# Zero_Crossing.net
KiCad netlist of a schematic drawn in Altium Designer
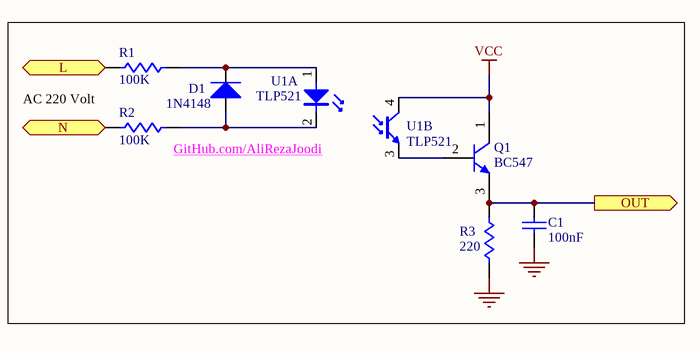
[diagram p0: Zero Crossing.SchDoc]

(export (version "E")
  (design (tool "Eeschema 10.0.6"))
  (components
    (comp (ref "C1")
      (value "100nF")
      (footprint "CAPNTO5.08-7.37x3.94")
      (description "Capacitor")
      (fields (field (name "MANUFACTURER") "Generic Components") (field (name "PUBLISHER") "Altium Limited"))
      (libsource (lib "Miscellaneous Devices") (part "Cap"))
    )
    (comp (ref "D1")
      (value "1N4148")
      (footprint "DIODE0.2_")
      (description "Default Diode")
      (fields (field (name "MANUFACTURER") "Generic Components") (field (name "PUBLISHER") "Altium Limited"))
      (libsource (lib "Miscellaneous Devices") (part "Diode"))
    )
    (comp (ref "Q1")
      (value "BC547")
      (footprint "TO92C")
      (description "Silicon Bipolar Transistor")
      (libsource (lib "my Libraries") (part "NPN"))
    )
    (comp (ref "R1")
      (value "100K")
      (footprint "AXIAL-0.4")
      (description "Resistor")
      (fields (field (name "MANUFACTURER") "Generic Components") (field (name "PUBLISHER") "Altium Limited"))
      (libsource (lib "Miscellaneous Devices") (part "Res1"))
    )
    (comp (ref "R2")
      (value "100K")
      (footprint "AXIAL-0.4")
      (description "Resistor")
      (fields (field (name "MANUFACTURER") "Generic Components") (field (name "PUBLISHER") "Altium Limited"))
      (libsource (lib "Miscellaneous Devices") (part "Res1"))
    )
    (comp (ref "R3")
      (value "220")
      (footprint "AXIAL-0.4")
      (description "Resistor")
      (fields (field (name "MANUFACTURER") "Generic Components") (field (name "PUBLISHER") "Altium Limited"))
      (libsource (lib "Miscellaneous Devices") (part "Res1"))
    )
    (comp (ref "U1")
      (value "TLP521")
      (footprint "DIP-4")
      (fields (field (name "PUBLISHER") "Altium Limited"))
      (libsource (lib "my Libraries") (part "Optoisolator"))
    )
  )
  (nets
    (net (code "1") (name "/L") (class "Default")
      (node (ref "R1") (pin "1") (pinfunction "1_1") (pintype "passive"))
    )
    (net (code "2") (name "/N") (class "Default")
      (node (ref "R2") (pin "1") (pinfunction "1_1") (pintype "passive"))
    )
    (net (code "3") (name "/OUT") (class "Default")
      (node (ref "C1") (pin "2") (pinfunction "2_2") (pintype "passive"))
      (node (ref "Q1") (pin "3") (pinfunction "E_3") (pintype "passive"))
      (node (ref "R3") (pin "1") (pinfunction "1_1") (pintype "passive"))
    )
    (net (code "4") (name "GND") (class "Default")
      (node (ref "C1") (pin "1") (pinfunction "1_1") (pintype "passive"))
      (node (ref "R3") (pin "2") (pinfunction "2_2") (pintype "passive"))
    )
    (net (code "5") (name "Net-(D1-A)") (class "Default")
      (node (ref "D1") (pin "1") (pinfunction "A_1") (pintype "passive"))
      (node (ref "R2") (pin "2") (pinfunction "2_2") (pintype "passive"))
      (node (ref "U1") (pin "2") (pinfunction "K_2") (pintype "power_in"))
    )
    (net (code "6") (name "Net-(D1-K)") (class "Default")
      (node (ref "D1") (pin "2") (pinfunction "K_2") (pintype "passive"))
      (node (ref "R1") (pin "2") (pinfunction "2_2") (pintype "passive"))
      (node (ref "U1") (pin "1") (pinfunction "A_1") (pintype "power_in"))
    )
    (net (code "7") (name "Net-(Q1-B)") (class "Default")
      (node (ref "Q1") (pin "2") (pinfunction "B_2") (pintype "passive"))
      (node (ref "U1") (pin "3") (pinfunction "E_3") (pintype "passive"))
    )
    (net (code "8") (name "VCC") (class "Default")
      (node (ref "Q1") (pin "1") (pinfunction "C_1") (pintype "passive"))
      (node (ref "U1") (pin "4") (pinfunction "C_4") (pintype "passive"))
    )
  )
)
